# VM_Motor_v0r.net
KiCad netlist of a schematic drawn in EAGLE
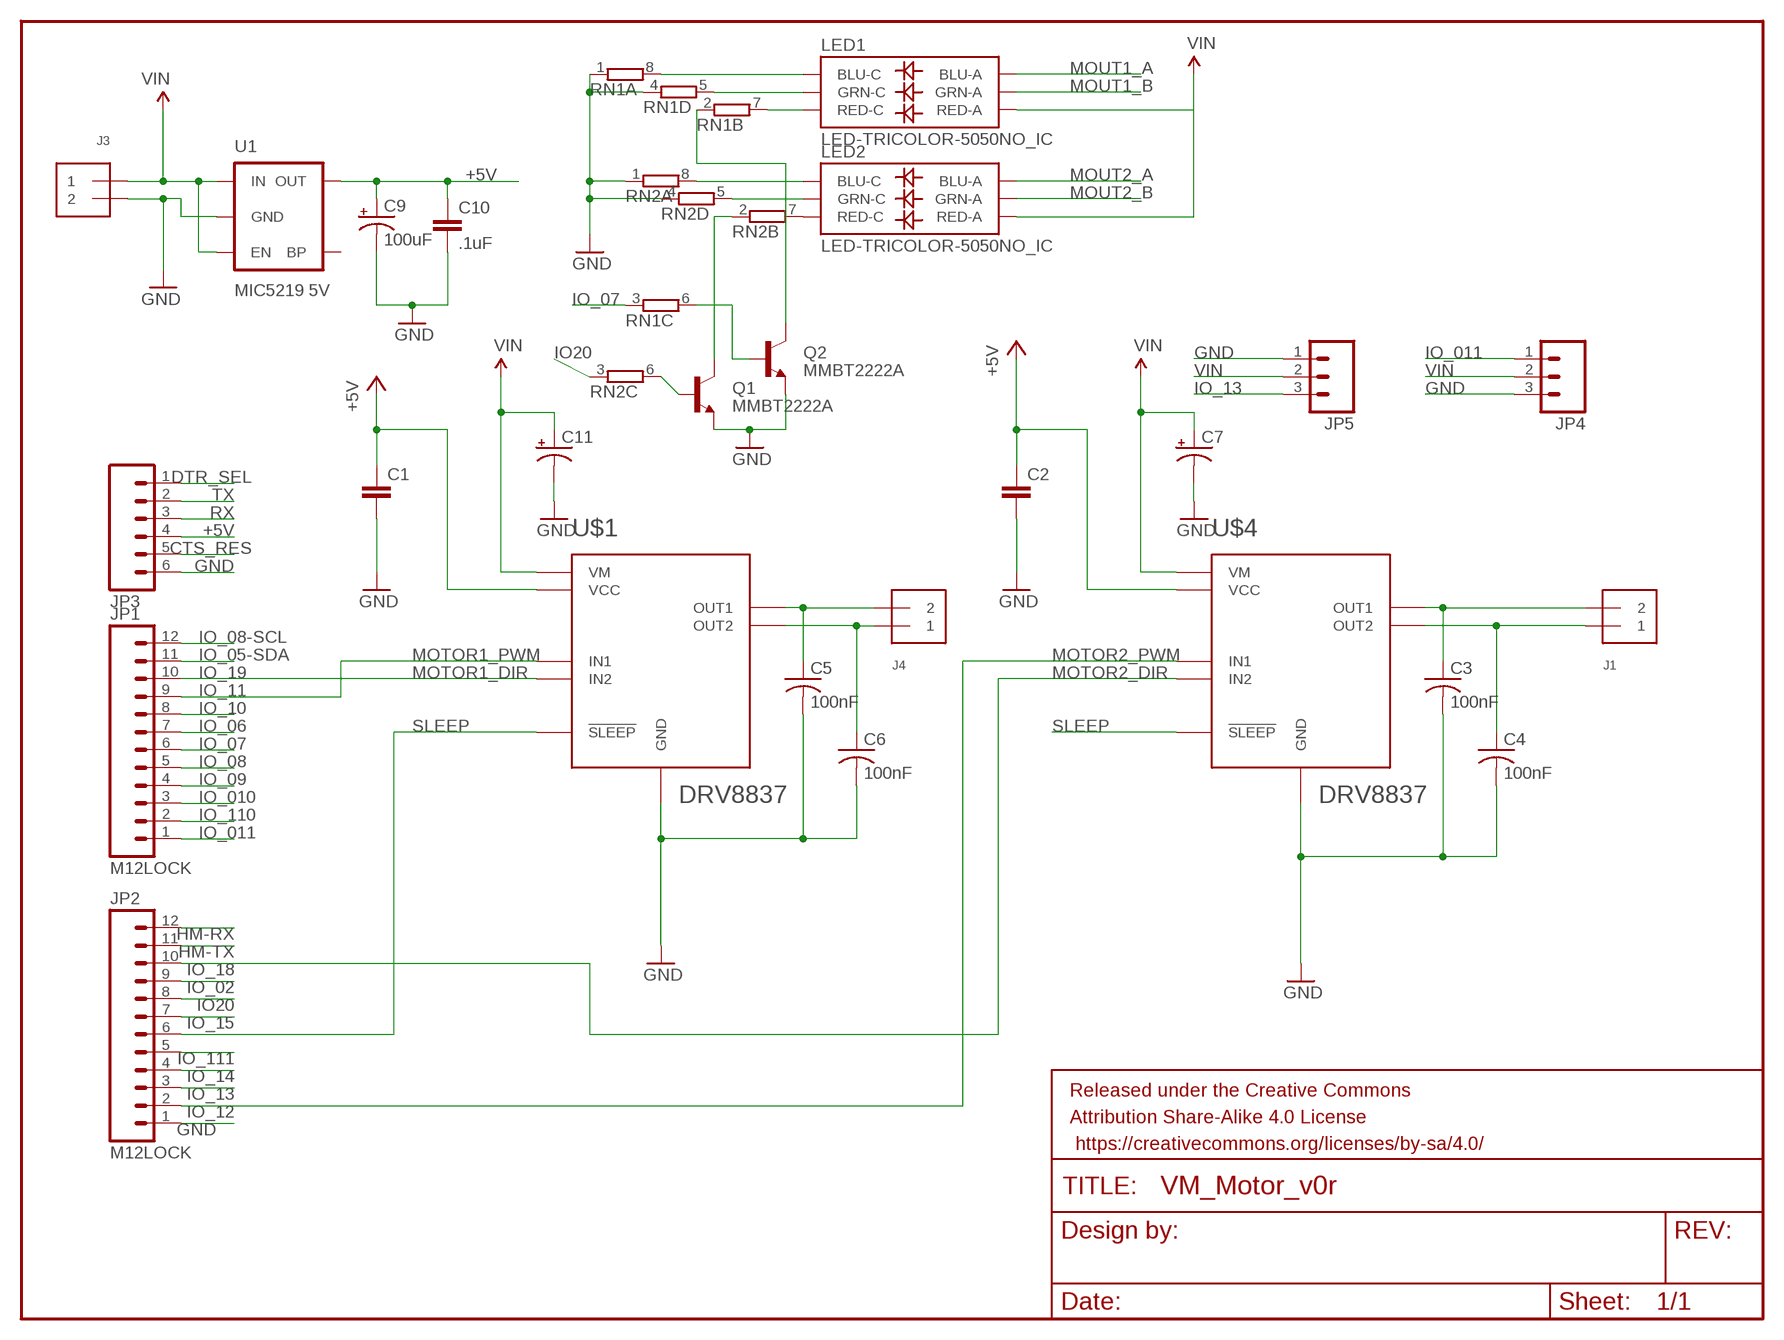
[diagram p0: schematic, sheet 1]

(export (version "E")
  (design (tool "Eeschema 10.0.6"))
  (components
    (comp (ref "C1")
      (value "CAP0402-CAP")
      (footprint "eagle-import:0402-CAP")
      (libsource (lib "eagle-import") (part "CAP0402-CAP"))
    )
    (comp (ref "C2")
      (value "CAP0402-CAP")
      (footprint "eagle-import:0402-CAP")
      (libsource (lib "eagle-import") (part "CAP0402-CAP"))
    )
    (comp (ref "C3")
      (value "100nF")
      (footprint "eagle-import:C0402")
      (libsource (lib "eagle-import") (part "C-USC0402"))
    )
    (comp (ref "C4")
      (value "100nF")
      (footprint "eagle-import:C0402")
      (libsource (lib "eagle-import") (part "C-USC0402"))
    )
    (comp (ref "C5")
      (value "100nF")
      (footprint "eagle-import:C0402")
      (libsource (lib "eagle-import") (part "C-USC0402"))
    )
    (comp (ref "C6")
      (value "100nF")
      (footprint "eagle-import:C0402")
      (libsource (lib "eagle-import") (part "C-USC0402"))
    )
    (comp (ref "C7")
      (value "CPOL-US140CLH-0810")
      (footprint "eagle-import:140CLH-0810")
      (libsource (lib "eagle-import") (part "CPOL-US140CLH-0810"))
    )
    (comp (ref "C9")
      (value "100uF")
      (footprint "eagle-import:EIA3528-KIT")
      (libsource (lib "eagle-import") (part "CAP_POL3528-KIT"))
    )
    (comp (ref "C10")
      (value ".1uF")
      (footprint "eagle-import:0402-CAP")
      (libsource (lib "eagle-import") (part "CAP0402-CAP"))
    )
    (comp (ref "C11")
      (value "CPOL-US140CLH-0810")
      (footprint "eagle-import:140CLH-0810")
      (libsource (lib "eagle-import") (part "CPOL-US140CLH-0810"))
    )
    (comp (ref "FRAME1")
      (value "FRAME-LETTER")
      (footprint "eagle-import:CREATIVE_COMMONS")
      (libsource (lib "eagle-import") (part "FRAME-LETTER"))
    )
    (comp (ref "J1")
      (value "TERMBLOCK_1X2")
      (footprint "eagle-import:TERMBLOCK_1X2-3.5MM")
      (libsource (lib "eagle-import") (part "TERMBLOCK_1X2"))
    )
    (comp (ref "J3")
      (value "TERMBLOCK_1X2")
      (footprint "eagle-import:TERMBLOCK_1X2-3.5MM")
      (libsource (lib "eagle-import") (part "TERMBLOCK_1X2"))
    )
    (comp (ref "J4")
      (value "TERMBLOCK_1X2")
      (footprint "eagle-import:TERMBLOCK_1X2-3.5MM")
      (libsource (lib "eagle-import") (part "TERMBLOCK_1X2"))
    )
    (comp (ref "JP1")
      (value "M12LOCK")
      (footprint "eagle-import:1X12_LOCK")
      (libsource (lib "eagle-import") (part "M12LOCK"))
    )
    (comp (ref "JP2")
      (value "M12LOCK")
      (footprint "eagle-import:1X12_LOCK")
      (libsource (lib "eagle-import") (part "M12LOCK"))
    )
    (comp (ref "JP3")
      (value "M06LOCK")
      (footprint "eagle-import:1X06_LOCK")
      (libsource (lib "eagle-import") (part "M06LOCK"))
    )
    (comp (ref "JP4")
      (value "M03LOCK")
      (footprint "eagle-import:1X03_LOCK")
      (libsource (lib "eagle-import") (part "M03LOCK"))
    )
    (comp (ref "JP5")
      (value "M03LOCK")
      (footprint "eagle-import:1X03_LOCK")
      (libsource (lib "eagle-import") (part "M03LOCK"))
    )
    (comp (ref "LED1")
      (value "LED-TRICOLOR-5050NO_IC")
      (footprint "eagle-import:LED-TRICOLOR-5050")
      (libsource (lib "eagle-import") (part "LED-TRICOLOR-5050NO_IC"))
    )
    (comp (ref "LED2")
      (value "LED-TRICOLOR-5050NO_IC")
      (footprint "eagle-import:LED-TRICOLOR-5050")
      (libsource (lib "eagle-import") (part "LED-TRICOLOR-5050NO_IC"))
    )
    (comp (ref "Q1")
      (value "MMBT2222A")
      (footprint "eagle-import:SOT23-3")
      (libsource (lib "eagle-import") (part "TRANSISTOR_NPNMMBT2222A"))
    )
    (comp (ref "Q2")
      (value "MMBT2222A")
      (footprint "eagle-import:SOT23-3")
      (libsource (lib "eagle-import") (part "TRANSISTOR_NPNMMBT2222A"))
    )
    (comp (ref "RN1")
      (value "4R-N0402ARV341")
      (footprint "eagle-import:4X0402ARV341")
      (libsource (lib "eagle-import") (part "4R-N0402ARV341"))
    )
    (comp (ref "RN2")
      (value "4R-N0402ARV341")
      (footprint "eagle-import:4X0402ARV341")
      (libsource (lib "eagle-import") (part "4R-N0402ARV341"))
    )
    (comp (ref "U$1")
      (value "DRV8837")
      (footprint "eagle-import:QFN8")
      (libsource (lib "eagle-import") (part "DRV8837"))
    )
    (comp (ref "U$4")
      (value "DRV8837")
      (footprint "eagle-import:QFN8")
      (libsource (lib "eagle-import") (part "DRV8837"))
    )
    (comp (ref "U1")
      (value "MIC5219 5V")
      (footprint "eagle-import:SOT23-5")
      (libsource (lib "eagle-import") (part "V_REG_MIC52195V"))
    )
  )
  (nets
    (net (code "1") (name "+5V") (class "Default")
      (node (ref "C1") (pin "1") (pinfunction "1_1") (pintype "passive"))
      (node (ref "C10") (pin "1") (pinfunction "1_1") (pintype "passive"))
      (node (ref "C2") (pin "1") (pinfunction "1_1") (pintype "passive"))
      (node (ref "C9") (pin "A") (pinfunction "+_A") (pintype "passive"))
      (node (ref "JP3") (pin "4") (pinfunction "4_4") (pintype "passive"))
      (node (ref "U$1") (pin "P$8") (pinfunction "VCC_P$8") (pintype "bidirectional"))
      (node (ref "U$4") (pin "P$8") (pinfunction "VCC_P$8") (pintype "bidirectional"))
      (node (ref "U1") (pin "5") (pinfunction "OUT_5") (pintype "passive"))
    )
    (net (code "2") (name "/CTS_RES") (class "Default")
      (node (ref "JP3") (pin "5") (pinfunction "5_5") (pintype "passive"))
    )
    (net (code "3") (name "/DTR_SEL") (class "Default")
      (node (ref "JP3") (pin "1") (pinfunction "1_1") (pintype "passive"))
    )
    (net (code "4") (name "/HM-RX") (class "Default")
      (node (ref "JP2") (pin "12") (pinfunction "12_12") (pintype "passive"))
    )
    (net (code "5") (name "/HM-TX") (class "Default")
      (node (ref "JP2") (pin "11") (pinfunction "11_11") (pintype "passive"))
    )
    (net (code "6") (name "/IO20") (class "Default")
      (node (ref "JP2") (pin "8") (pinfunction "8_8") (pintype "passive"))
      (node (ref "RN2") (pin "3") (pinfunction "1_3") (pintype "passive"))
    )
    (net (code "7") (name "/IO_02") (class "Default")
      (node (ref "JP2") (pin "9") (pinfunction "9_9") (pintype "passive"))
    )
    (net (code "8") (name "/IO_05-SDA") (class "Default")
      (node (ref "JP1") (pin "11") (pinfunction "11_11") (pintype "passive"))
    )
    (net (code "9") (name "/IO_06") (class "Default")
      (node (ref "JP1") (pin "7") (pinfunction "7_7") (pintype "passive"))
    )
    (net (code "10") (name "/IO_07") (class "Default")
      (node (ref "JP1") (pin "6") (pinfunction "6_6") (pintype "passive"))
      (node (ref "RN1") (pin "3") (pinfunction "1_3") (pintype "passive"))
    )
    (net (code "11") (name "/IO_08") (class "Default")
      (node (ref "JP1") (pin "5") (pinfunction "5_5") (pintype "passive"))
    )
    (net (code "12") (name "/IO_08-SCL") (class "Default")
      (node (ref "JP1") (pin "12") (pinfunction "12_12") (pintype "passive"))
    )
    (net (code "13") (name "/IO_09") (class "Default")
      (node (ref "JP1") (pin "4") (pinfunction "4_4") (pintype "passive"))
    )
    (net (code "14") (name "/IO_10") (class "Default")
      (node (ref "JP1") (pin "8") (pinfunction "8_8") (pintype "passive"))
    )
    (net (code "15") (name "/IO_010") (class "Default")
      (node (ref "JP1") (pin "3") (pinfunction "3_3") (pintype "passive"))
    )
    (net (code "16") (name "/IO_011") (class "Default")
      (node (ref "JP1") (pin "1") (pinfunction "1_1") (pintype "passive"))
      (node (ref "JP4") (pin "1") (pinfunction "1_1") (pintype "passive"))
    )
    (net (code "17") (name "/IO_13") (class "Default")
      (node (ref "JP2") (pin "3") (pinfunction "3_3") (pintype "passive"))
      (node (ref "JP5") (pin "3") (pinfunction "3_3") (pintype "passive"))
    )
    (net (code "18") (name "/IO_14") (class "Default")
      (node (ref "JP2") (pin "4") (pinfunction "4_4") (pintype "passive"))
    )
    (net (code "19") (name "/IO_15") (class "Default")
      (node (ref "JP2") (pin "7") (pinfunction "7_7") (pintype "passive"))
    )
    (net (code "20") (name "/IO_110") (class "Default")
      (node (ref "JP1") (pin "2") (pinfunction "2_2") (pintype "passive"))
    )
    (net (code "21") (name "/IO_111") (class "Default")
      (node (ref "JP2") (pin "5") (pinfunction "5_5") (pintype "passive"))
    )
    (net (code "22") (name "/MOTOR1_DIR") (class "Default")
      (node (ref "JP1") (pin "10") (pinfunction "10_10") (pintype "passive"))
      (node (ref "U$1") (pin "P$5") (pinfunction "IN2_P$5") (pintype "bidirectional"))
    )
    (net (code "23") (name "/MOTOR1_PWM") (class "Default")
      (node (ref "JP1") (pin "9") (pinfunction "9_9") (pintype "passive"))
      (node (ref "U$1") (pin "P$6") (pinfunction "IN1_P$6") (pintype "bidirectional"))
    )
    (net (code "24") (name "/MOTOR2_DIR") (class "Default")
      (node (ref "JP2") (pin "10") (pinfunction "10_10") (pintype "passive"))
      (node (ref "U$4") (pin "P$5") (pinfunction "IN2_P$5") (pintype "bidirectional"))
    )
    (net (code "25") (name "/MOTOR2_PWM") (class "Default")
      (node (ref "JP2") (pin "2") (pinfunction "2_2") (pintype "passive"))
      (node (ref "U$4") (pin "P$6") (pinfunction "IN1_P$6") (pintype "bidirectional"))
    )
    (net (code "26") (name "/MOUT1_A") (class "Default")
      (node (ref "C5") (pin "1") (pinfunction "1_1") (pintype "passive"))
      (node (ref "J4") (pin "2") (pinfunction "2_2") (pintype "passive"))
      (node (ref "LED1") (pin "3") (pinfunction "BLU-A_3") (pintype "bidirectional"))
      (node (ref "U$1") (pin "P$2") (pinfunction "OUT1_P$2") (pintype "bidirectional"))
    )
    (net (code "27") (name "/MOUT1_B") (class "Default")
      (node (ref "C6") (pin "1") (pinfunction "1_1") (pintype "passive"))
      (node (ref "J4") (pin "1") (pinfunction "1_1") (pintype "passive"))
      (node (ref "LED1") (pin "1") (pinfunction "GRN-A_1") (pintype "bidirectional"))
      (node (ref "U$1") (pin "P$3") (pinfunction "OUT2_P$3") (pintype "bidirectional"))
    )
    (net (code "28") (name "/MOUT2_A") (class "Default")
      (node (ref "C3") (pin "1") (pinfunction "1_1") (pintype "passive"))
      (node (ref "J1") (pin "2") (pinfunction "2_2") (pintype "passive"))
      (node (ref "LED2") (pin "3") (pinfunction "BLU-A_3") (pintype "bidirectional"))
      (node (ref "U$4") (pin "P$2") (pinfunction "OUT1_P$2") (pintype "bidirectional"))
    )
    (net (code "29") (name "/MOUT2_B") (class "Default")
      (node (ref "C4") (pin "1") (pinfunction "1_1") (pintype "passive"))
      (node (ref "J1") (pin "1") (pinfunction "1_1") (pintype "passive"))
      (node (ref "LED2") (pin "1") (pinfunction "GRN-A_1") (pintype "bidirectional"))
      (node (ref "U$4") (pin "P$3") (pinfunction "OUT2_P$3") (pintype "bidirectional"))
    )
    (net (code "30") (name "/RX") (class "Default")
      (node (ref "JP3") (pin "3") (pinfunction "3_3") (pintype "passive"))
    )
    (net (code "31") (name "/SLEEP") (class "Default")
      (node (ref "JP2") (pin "6") (pinfunction "6_6") (pintype "passive"))
      (node (ref "U$1") (pin "P$7") (pinfunction "~{SLEEP}_P$7") (pintype "bidirectional"))
      (node (ref "U$4") (pin "P$7") (pinfunction "~{SLEEP}_P$7") (pintype "bidirectional"))
    )
    (net (code "32") (name "/TX") (class "Default")
      (node (ref "JP3") (pin "2") (pinfunction "2_2") (pintype "passive"))
    )
    (net (code "33") (name "GND") (class "Default")
      (node (ref "C1") (pin "2") (pinfunction "2_2") (pintype "passive"))
      (node (ref "C10") (pin "2") (pinfunction "2_2") (pintype "passive"))
      (node (ref "C11") (pin "-") (pinfunction "-_-") (pintype "passive"))
      (node (ref "C2") (pin "2") (pinfunction "2_2") (pintype "passive"))
      (node (ref "C3") (pin "2") (pinfunction "2_2") (pintype "passive"))
      (node (ref "C4") (pin "2") (pinfunction "2_2") (pintype "passive"))
      (node (ref "C5") (pin "2") (pinfunction "2_2") (pintype "passive"))
      (node (ref "C6") (pin "2") (pinfunction "2_2") (pintype "passive"))
      (node (ref "C7") (pin "-") (pinfunction "-_-") (pintype "passive"))
      (node (ref "C9") (pin "C") (pinfunction "-_C") (pintype "passive"))
      (node (ref "J3") (pin "2") (pinfunction "2_2") (pintype "passive"))
      (node (ref "JP2") (pin "1") (pinfunction "1_1") (pintype "passive"))
      (node (ref "JP3") (pin "6") (pinfunction "6_6") (pintype "passive"))
      (node (ref "JP4") (pin "3") (pinfunction "3_3") (pintype "passive"))
      (node (ref "JP5") (pin "1") (pinfunction "1_1") (pintype "passive"))
      (node (ref "Q1") (pin "2") (pinfunction "E_2") (pintype "passive"))
      (node (ref "Q2") (pin "2") (pinfunction "E_2") (pintype "passive"))
      (node (ref "RN1") (pin "1") (pinfunction "1_1") (pintype "passive"))
      (node (ref "RN1") (pin "4") (pinfunction "1_4") (pintype "passive"))
      (node (ref "RN2") (pin "1") (pinfunction "1_1") (pintype "passive"))
      (node (ref "RN2") (pin "4") (pinfunction "1_4") (pintype "passive"))
      (node (ref "U$1") (pin "P$10") (pinfunction "GND_P$10") (pintype "bidirectional"))
      (node (ref "U$1") (pin "P$11") (pinfunction "GND_P$11") (pintype "bidirectional"))
      (node (ref "U$1") (pin "P$4") (pinfunction "GND_P$4") (pintype "bidirectional"))
      (node (ref "U$1") (pin "P$9") (pinfunction "GND_P$9") (pintype "bidirectional"))
      (node (ref "U$4") (pin "P$10") (pinfunction "GND_P$10") (pintype "bidirectional"))
      (node (ref "U$4") (pin "P$11") (pinfunction "GND_P$11") (pintype "bidirectional"))
      (node (ref "U$4") (pin "P$4") (pinfunction "GND_P$4") (pintype "bidirectional"))
      (node (ref "U$4") (pin "P$9") (pinfunction "GND_P$9") (pintype "bidirectional"))
      (node (ref "U1") (pin "2") (pinfunction "GND_2") (pintype "input"))
    )
    (net (code "34") (name "Net-(LED1-BLU-C)") (class "Default")
      (node (ref "LED1") (pin "4") (pinfunction "BLU-C_4") (pintype "bidirectional"))
      (node (ref "RN1") (pin "8") (pinfunction "2_8") (pintype "passive"))
    )
    (net (code "35") (name "Net-(LED1-GRN-C)") (class "Default")
      (node (ref "LED1") (pin "6") (pinfunction "GRN-C_6") (pintype "bidirectional"))
      (node (ref "RN1") (pin "5") (pinfunction "2_5") (pintype "passive"))
    )
    (net (code "36") (name "Net-(LED1-RED-C)") (class "Default")
      (node (ref "LED1") (pin "5") (pinfunction "RED-C_5") (pintype "bidirectional"))
      (node (ref "RN1") (pin "7") (pinfunction "2_7") (pintype "passive"))
    )
    (net (code "37") (name "Net-(LED2-BLU-C)") (class "Default")
      (node (ref "LED2") (pin "4") (pinfunction "BLU-C_4") (pintype "bidirectional"))
      (node (ref "RN2") (pin "8") (pinfunction "2_8") (pintype "passive"))
    )
    (net (code "38") (name "Net-(LED2-GRN-C)") (class "Default")
      (node (ref "LED2") (pin "6") (pinfunction "GRN-C_6") (pintype "bidirectional"))
      (node (ref "RN2") (pin "5") (pinfunction "2_5") (pintype "passive"))
    )
    (net (code "39") (name "Net-(LED2-RED-C)") (class "Default")
      (node (ref "LED2") (pin "5") (pinfunction "RED-C_5") (pintype "bidirectional"))
      (node (ref "RN2") (pin "7") (pinfunction "2_7") (pintype "passive"))
    )
    (net (code "40") (name "Net-(Q1-B)") (class "Default")
      (node (ref "Q1") (pin "1") (pinfunction "B_1") (pintype "passive"))
      (node (ref "RN2") (pin "6") (pinfunction "2_6") (pintype "passive"))
    )
    (net (code "41") (name "Net-(Q1-C)") (class "Default")
      (node (ref "Q1") (pin "3") (pinfunction "C_3") (pintype "passive"))
      (node (ref "RN2") (pin "2") (pinfunction "1_2") (pintype "passive"))
    )
    (net (code "42") (name "Net-(Q2-B)") (class "Default")
      (node (ref "Q2") (pin "1") (pinfunction "B_1") (pintype "passive"))
      (node (ref "RN1") (pin "6") (pinfunction "2_6") (pintype "passive"))
    )
    (net (code "43") (name "Net-(Q2-C)") (class "Default")
      (node (ref "Q2") (pin "3") (pinfunction "C_3") (pintype "passive"))
      (node (ref "RN1") (pin "2") (pinfunction "1_2") (pintype "passive"))
    )
    (net (code "44") (name "VIN") (class "Default")
      (node (ref "C11") (pin "+") (pinfunction "+_+") (pintype "passive"))
      (node (ref "C7") (pin "+") (pinfunction "+_+") (pintype "passive"))
      (node (ref "J3") (pin "1") (pinfunction "1_1") (pintype "passive"))
      (node (ref "JP4") (pin "2") (pinfunction "2_2") (pintype "passive"))
      (node (ref "JP5") (pin "2") (pinfunction "2_2") (pintype "passive"))
      (node (ref "LED1") (pin "2") (pinfunction "RED-A_2") (pintype "bidirectional"))
      (node (ref "LED2") (pin "2") (pinfunction "RED-A_2") (pintype "bidirectional"))
      (node (ref "U$1") (pin "P$1") (pinfunction "VM_P$1") (pintype "bidirectional"))
      (node (ref "U$4") (pin "P$1") (pinfunction "VM_P$1") (pintype "bidirectional"))
      (node (ref "U1") (pin "1") (pinfunction "IN_1") (pintype "input"))
      (node (ref "U1") (pin "3") (pinfunction "EN_3") (pintype "input"))
    )
    (net (code "45") (name "unconnected-(U1-BP-Pad4)") (class "Default")
      (node (ref "U1") (pin "4") (pinfunction "BP_4") (pintype "input"))
    )
  )
)
